# S-ONDAS-ESPIN.net
KiCad netlist of a schematic drawn in Altium Designer
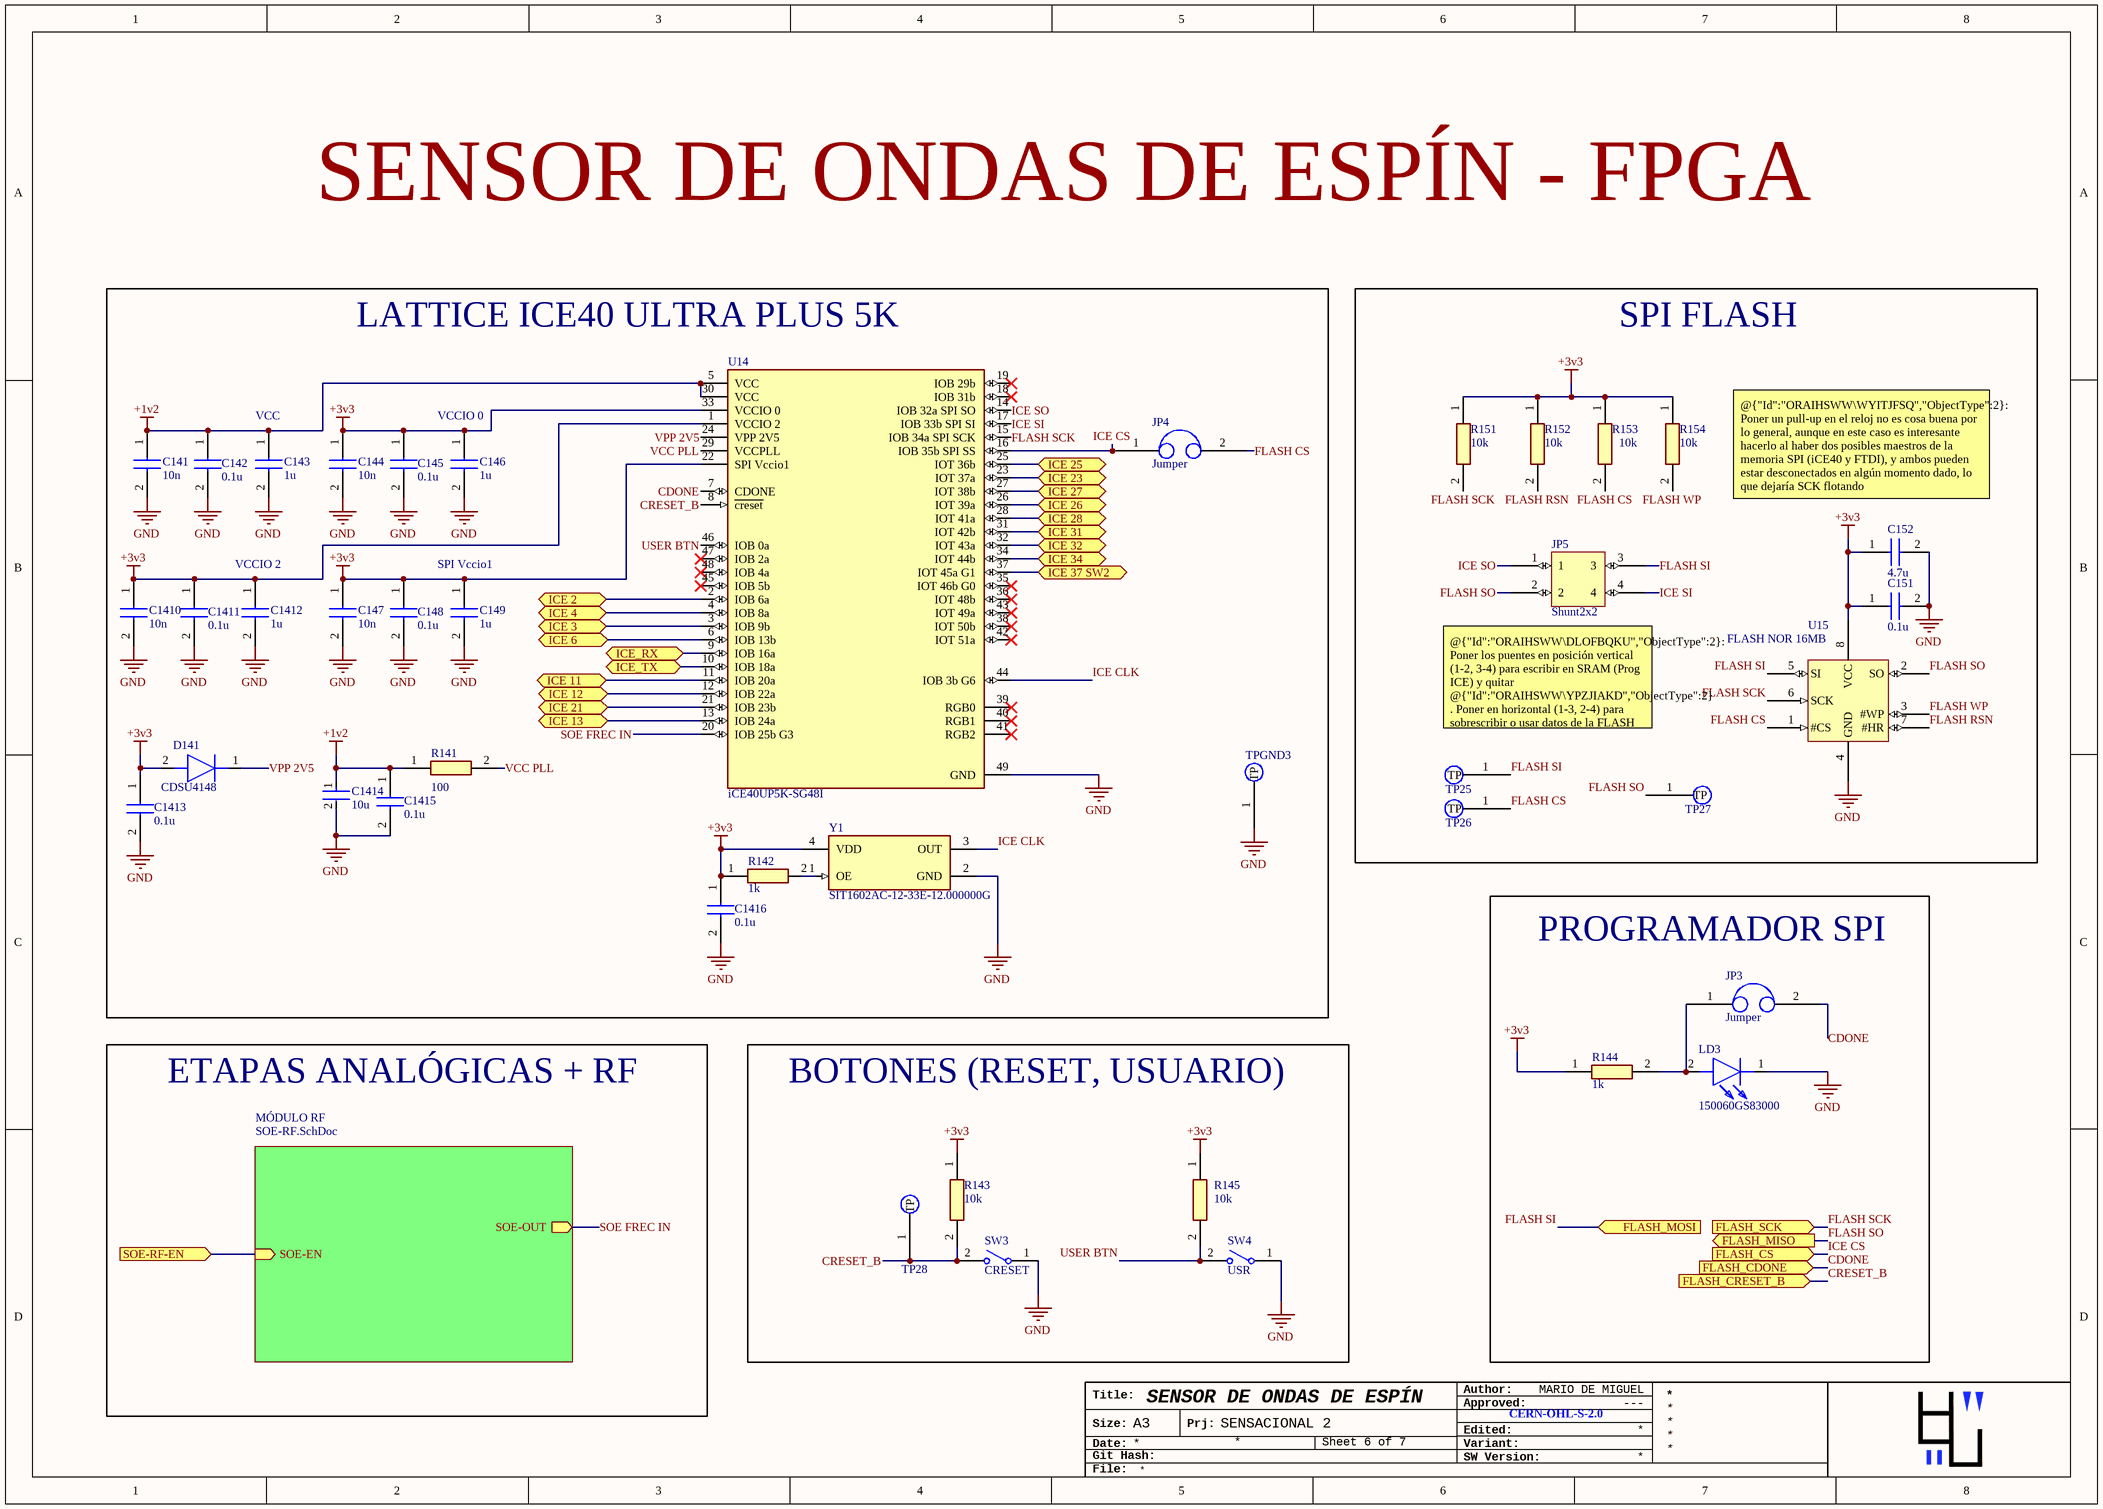
[diagram p0: S-ONDAS-ESPIN.SchDoc]

(export (version "E")
  (design (tool "Eeschema 10.0.6"))
  (components
    (comp (ref "C141")
      (value "10n")
      (footprint "SamacSys:CAPC1005X55N")
      (description "Capacitor")
      (fields (field (name "MANUFACTURER_PART_NUMBER") "GXT155R71E103KE01D"))
      (libsource (lib "*") (part "GXT155R71E103KE01D"))
    )
    (comp (ref "C142")
      (value "0.1u")
      (footprint "SamacSys:CAPC1005X22N")
      (description "Capacitor")
      (fields
        (field (name "MANUFACTURER_PART_NUMBER") "GRM152R61A104KE19D")
        (field (name "MOUSER PART NUMBER") "81-GRM152R61A104KE9D")
      )
      (libsource (lib "*") (part "GRM152R61A104KE19D"))
    )
    (comp (ref "C143")
      (value "1u")
      (footprint "SamacSys:GRM15x")
      (description "Capacitor")
      (fields (field (name "MANUFACTURER_PART_NUMBER") "GRM155C71C105ME11J"))
      (libsource (lib "*") (part "GRM155C71C105ME11J"))
    )
    (comp (ref "C144")
      (value "10n")
      (footprint "SamacSys:CAPC1005X55N")
      (description "Capacitor")
      (fields (field (name "MANUFACTURER_PART_NUMBER") "GXT155R71E103KE01D"))
      (libsource (lib "*") (part "GXT155R71E103KE01D"))
    )
    (comp (ref "C145")
      (value "0.1u")
      (footprint "SamacSys:CAPC1005X22N")
      (description "Capacitor")
      (fields
        (field (name "MANUFACTURER_PART_NUMBER") "GRM152R61A104KE19D")
        (field (name "MOUSER PART NUMBER") "81-GRM152R61A104KE9D")
      )
      (libsource (lib "*") (part "GRM152R61A104KE19D"))
    )
    (comp (ref "C146")
      (value "1u")
      (footprint "SamacSys:GRM15x")
      (description "Capacitor")
      (fields (field (name "MANUFACTURER_PART_NUMBER") "GRM155C71C105ME11J"))
      (libsource (lib "*") (part "GRM155C71C105ME11J"))
    )
    (comp (ref "C147")
      (value "10n")
      (footprint "SamacSys:CAPC1005X55N")
      (description "Capacitor")
      (fields (field (name "MANUFACTURER_PART_NUMBER") "GXT155R71E103KE01D"))
      (libsource (lib "*") (part "GXT155R71E103KE01D"))
    )
    (comp (ref "C148")
      (value "0.1u")
      (footprint "SamacSys:CAPC1005X22N")
      (description "Capacitor")
      (fields
        (field (name "MANUFACTURER_PART_NUMBER") "GRM152R61A104KE19D")
        (field (name "MOUSER PART NUMBER") "81-GRM152R61A104KE9D")
      )
      (libsource (lib "*") (part "GRM152R61A104KE19D"))
    )
    (comp (ref "C149")
      (value "1u")
      (footprint "SamacSys:GRM15x")
      (description "Capacitor")
      (fields (field (name "MANUFACTURER_PART_NUMBER") "GRM155C71C105ME11J"))
      (libsource (lib "*") (part "GRM155C71C105ME11J"))
    )
    (comp (ref "C151")
      (value "0.1u")
      (footprint "SamacSys:CAPC1005X22N")
      (description "Capacitor")
      (fields
        (field (name "MANUFACTURER_PART_NUMBER") "GRM152R61A104KE19D")
        (field (name "MOUSER PART NUMBER") "81-GRM152R61A104KE9D")
      )
      (libsource (lib "*") (part "GRM152R61A104KE19D"))
    )
    (comp (ref "C152")
      (value "4.7u")
      (footprint "SamacSys:C0805")
      (description "Capacitor")
      (fields
        (field (name "MANUFACTURER_PART_NUMBER") "C0805X475J8RACAUTO")
        (field (name "MOUSER PART NUMBER") "80-C0805X475J8RAUTO")
      )
      (libsource (lib "*") (part "C0805X475J8RACAUTO"))
    )
    (comp (ref "C1410")
      (value "10n")
      (footprint "SamacSys:CAPC1005X55N")
      (description "Capacitor")
      (fields (field (name "MANUFACTURER_PART_NUMBER") "GXT155R71E103KE01D"))
      (libsource (lib "*") (part "GXT155R71E103KE01D"))
    )
    (comp (ref "C1411")
      (value "0.1u")
      (footprint "SamacSys:CAPC1005X22N")
      (description "Capacitor")
      (fields
        (field (name "MANUFACTURER_PART_NUMBER") "GRM152R61A104KE19D")
        (field (name "MOUSER PART NUMBER") "81-GRM152R61A104KE9D")
      )
      (libsource (lib "*") (part "GRM152R61A104KE19D"))
    )
    (comp (ref "C1412")
      (value "1u")
      (footprint "SamacSys:GRM15x")
      (description "Capacitor")
      (fields (field (name "MANUFACTURER_PART_NUMBER") "GRM155C71C105ME11J"))
      (libsource (lib "*") (part "GRM155C71C105ME11J"))
    )
    (comp (ref "C1413")
      (value "0.1u")
      (footprint "SamacSys:CAPC1005X22N")
      (description "Capacitor")
      (fields
        (field (name "MANUFACTURER_PART_NUMBER") "GRM152R61A104KE19D")
        (field (name "MOUSER PART NUMBER") "81-GRM152R61A104KE9D")
      )
      (libsource (lib "*") (part "GRM152R61A104KE19D"))
    )
    (comp (ref "C1414")
      (value "10u")
      (footprint "FP-C2012-125-0_2-MFG")
      (description "Multilayer Ceramic Capacitors 10μF ±10% 10V X7R SMD 0805")
      (fields (field (name "TOLERANCE") "10%") (field (name "VOLTAGE") "10V"))
      (libsource (lib "Altium Content Vault") (part "b4654b650e69147ec39a6b967a45e02"))
    )
    (comp (ref "C1415")
      (value "0.1u")
      (footprint "SamacSys:CAPC1005X22N")
      (description "Capacitor")
      (fields
        (field (name "MANUFACTURER_PART_NUMBER") "GRM152R61A104KE19D")
        (field (name "MOUSER PART NUMBER") "81-GRM152R61A104KE9D")
      )
      (libsource (lib "*") (part "GRM152R61A104KE19D"))
    )
    (comp (ref "C1416")
      (value "0.1u")
      (footprint "SamacSys:CAPC1005X22N")
      (description "Capacitor")
      (fields
        (field (name "MANUFACTURER_PART_NUMBER") "GRM152R61A104KE19D")
        (field (name "MOUSER PART NUMBER") "81-GRM152R61A104KE9D")
      )
      (libsource (lib "*") (part "GRM152R61A104KE19D"))
    )
    (comp (ref "D141")
      (value "CDSU4148")
      (footprint "SamacSys:DIOM179X85N")
      (description "Diode")
      (fields (field (name "MOUSER PART NUMBER") "750-CDSU4148"))
      (libsource (lib "*") (part "CDSU4148"))
    )
    (comp (ref "JP3") (value "Jumper") (footprint "JUMPER_SHUNT") (libsource (lib "headers") (part "Shunt")))
    (comp (ref "JP4") (value "Jumper") (footprint "JUMPER_SHUNT") (libsource (lib "headers") (part "Shunt")))
    (comp (ref "JP5")
      (value "Shunt2x2")
      (footprint "JUMPER_SHUNT2X2")
      (libsource (lib "headers") (part "Shunt2x2"))
    )
    (comp (ref "LD3")
      (value "150060GS83000")
      (footprint "SamacSys:LEDC1608X95N")
      (description "LED")
      (libsource (lib "*") (part "150060GS83000"))
    )
    (comp (ref "R141")
      (value "100")
      (footprint "SamacSys:RESC1608X50N")
      (description "Resistor")
      (fields
        (field (name "MANUFACTURER_PART_NUMBER") "RCG0603100RJNEA")
        (field (name "MOUSER PART NUMBER") "71-RCG0603100RJNEA")
      )
      (libsource (lib "*") (part "RCG0603100RJNEA"))
    )
    (comp (ref "R142")
      (value "1k")
      (footprint "SamacSys:ERA6AEB101V")
      (description "Resistor")
      (fields
        (field (name "MANUFACTURER_PART_NUMBER") "ERA-6ARW102V")
        (field (name "MOUSER PART NUMBER") "667-ERA-6ARW102V")
      )
      (libsource (lib "*") (part "ERA-6ARW102V"))
    )
    (comp (ref "R143")
      (value "10k")
      (footprint "SamacSys:RESC1005X40N")
      (description "Resistor")
      (fields
        (field (name "MANUFACTURER_PART_NUMBER") "RCA040210K0JNED")
        (field (name "MOUSER PART NUMBER") "71-RCA040210K0JNED")
      )
      (libsource (lib "*") (part "RCA040210K0JNED"))
    )
    (comp (ref "R144")
      (value "1k")
      (footprint "SamacSys:ERA6AEB101V")
      (description "Resistor")
      (fields
        (field (name "MANUFACTURER_PART_NUMBER") "ERA-6ARW102V")
        (field (name "MOUSER PART NUMBER") "667-ERA-6ARW102V")
      )
      (libsource (lib "*") (part "ERA-6ARW102V"))
    )
    (comp (ref "R145")
      (value "10k")
      (footprint "SamacSys:RESC1005X40N")
      (description "Resistor")
      (fields
        (field (name "MANUFACTURER_PART_NUMBER") "RCA040210K0JNED")
        (field (name "MOUSER PART NUMBER") "71-RCA040210K0JNED")
      )
      (libsource (lib "*") (part "RCA040210K0JNED"))
    )
    (comp (ref "R151")
      (value "10k")
      (footprint "SamacSys:RESC1005X40N")
      (description "Resistor")
      (fields
        (field (name "MANUFACTURER_PART_NUMBER") "RCA040210K0JNED")
        (field (name "MOUSER PART NUMBER") "71-RCA040210K0JNED")
      )
      (libsource (lib "*") (part "RCA040210K0JNED"))
    )
    (comp (ref "R152")
      (value "10k")
      (footprint "SamacSys:RESC1005X40N")
      (description "Resistor")
      (fields
        (field (name "MANUFACTURER_PART_NUMBER") "RCA040210K0JNED")
        (field (name "MOUSER PART NUMBER") "71-RCA040210K0JNED")
      )
      (libsource (lib "*") (part "RCA040210K0JNED"))
    )
    (comp (ref "R153")
      (value "10k")
      (footprint "SamacSys:RESC1005X40N")
      (description "Resistor")
      (fields
        (field (name "MANUFACTURER_PART_NUMBER") "RCA040210K0JNED")
        (field (name "MOUSER PART NUMBER") "71-RCA040210K0JNED")
      )
      (libsource (lib "*") (part "RCA040210K0JNED"))
    )
    (comp (ref "R154")
      (value "10k")
      (footprint "SamacSys:RESC1005X40N")
      (description "Resistor")
      (fields
        (field (name "MANUFACTURER_PART_NUMBER") "RCA040210K0JNED")
        (field (name "MOUSER PART NUMBER") "71-RCA040210K0JNED")
      )
      (libsource (lib "*") (part "RCA040210K0JNED"))
    )
    (comp (ref "SW3")
      (value "CRESET")
      (footprint "434121025816")
      (description "Switch Tactile Spst-no 0.05A 12V")
      (libsource (lib "Altium Content Vault") (part "SPST-NO_2P"))
    )
    (comp (ref "SW4")
      (value "USR")
      (footprint "434121025816")
      (description "Switch Tactile Spst-no 0.05A 12V")
      (libsource (lib "Altium Content Vault") (part "SPST-NO_2P"))
    )
    (comp (ref "TP25")
      (value "Testpoint")
      (footprint "TESTPOINT_SMD")
      (libsource (lib "headers") (part "Testpoint"))
    )
    (comp (ref "TP26")
      (value "Testpoint")
      (footprint "TESTPOINT_SMD")
      (libsource (lib "headers") (part "Testpoint"))
    )
    (comp (ref "TP27")
      (value "Testpoint")
      (footprint "TESTPOINT_SMD")
      (libsource (lib "headers") (part "Testpoint"))
    )
    (comp (ref "TP28")
      (value "Testpoint")
      (footprint "Testpoint_TH")
      (libsource (lib "headers") (part "Testpoint"))
    )
    (comp (ref "TPGND3")
      (value "Testpoint")
      (footprint "Testpoint_TH")
      (libsource (lib "headers") (part "Testpoint"))
    )
    (comp (ref "U14")
      (value "iCE40UP5K-SG48I")
      (footprint "FP-QFN-48-IPC_C")
      (description "ICE40-ULTRAPLUS, 5280 LUTS, 1.2V")
      (fields
        (field (name "MANUFACTURER") "Lattice")
        (field (name "OCTOPART") "https://octopart.com/ice40up5k-sg48i-lattice+semiconductor-87369311")
      )
      (libsource (lib "Altium Content Vault") (part "90c839ece6b9b86f6dd6a74a4566a88"))
    )
    (comp (ref "U15")
      (value "FLASH NOR 16MB")
      (footprint "SOIC127P790X216-8N:SOIC127P790X216-8N")
      (libsource (lib "IS25LP016D-JBLE") (part "IS25LP016D-JBLE"))
    )
    (comp (ref "Y1")
      (value "SIT1602AC-12-33E-12.000000G")
      (footprint "FP-SiT1602-1-MFG")
      (description "MEMS OSC XO 12.0000MHZ LVCMOS")
      (libsource (lib "Altium Content Vault") (part "ab5556b3551095060e619687c253883"))
    )
  )
  (nets
    (net (code "1") (name "+1v2") (class "Default")
      (node (ref "C141") (pin "1") (pinfunction "1_1") (pintype "passive"))
      (node (ref "C1414") (pin "1") (pinfunction "1_1") (pintype "passive"))
      (node (ref "C1415") (pin "1") (pinfunction "1_1") (pintype "passive"))
      (node (ref "C142") (pin "1") (pinfunction "1_1") (pintype "passive"))
      (node (ref "C143") (pin "1") (pinfunction "1_1") (pintype "passive"))
      (node (ref "R141") (pin "1") (pinfunction "1_1") (pintype "passive"))
      (node (ref "U14") (pin "30") (pinfunction "VCC_30") (pintype "power_in"))
      (node (ref "U14") (pin "5") (pinfunction "VCC_5") (pintype "power_in"))
    )
    (net (code "2") (name "+3v3") (class "Default")
      (node (ref "C1410") (pin "1") (pinfunction "1_1") (pintype "passive"))
      (node (ref "C1411") (pin "1") (pinfunction "1_1") (pintype "passive"))
      (node (ref "C1412") (pin "1") (pinfunction "1_1") (pintype "passive"))
      (node (ref "C1413") (pin "1") (pinfunction "1_1") (pintype "passive"))
      (node (ref "C1416") (pin "1") (pinfunction "1_1") (pintype "passive"))
      (node (ref "C144") (pin "1") (pinfunction "1_1") (pintype "passive"))
      (node (ref "C145") (pin "1") (pinfunction "1_1") (pintype "passive"))
      (node (ref "C146") (pin "1") (pinfunction "1_1") (pintype "passive"))
      (node (ref "C147") (pin "1") (pinfunction "1_1") (pintype "passive"))
      (node (ref "C148") (pin "1") (pinfunction "1_1") (pintype "passive"))
      (node (ref "C149") (pin "1") (pinfunction "1_1") (pintype "passive"))
      (node (ref "C151") (pin "1") (pinfunction "1_1") (pintype "passive"))
      (node (ref "C152") (pin "1") (pinfunction "1_1") (pintype "passive"))
      (node (ref "D141") (pin "2") (pinfunction "A_2") (pintype "passive"))
      (node (ref "R142") (pin "1") (pinfunction "1_1") (pintype "passive"))
      (node (ref "R143") (pin "1") (pinfunction "1_1") (pintype "passive"))
      (node (ref "R144") (pin "1") (pinfunction "1_1") (pintype "passive"))
      (node (ref "R145") (pin "1") (pinfunction "1_1") (pintype "passive"))
      (node (ref "R151") (pin "1") (pinfunction "1_1") (pintype "passive"))
      (node (ref "R152") (pin "1") (pinfunction "1_1") (pintype "passive"))
      (node (ref "R153") (pin "1") (pinfunction "1_1") (pintype "passive"))
      (node (ref "R154") (pin "1") (pinfunction "1_1") (pintype "passive"))
      (node (ref "U14") (pin "1") (pinfunction "VCCIO_2_1") (pintype "power_in"))
      (node (ref "U14") (pin "22") (pinfunction "SPI_Vccio1_22") (pintype "power_in"))
      (node (ref "U14") (pin "33") (pinfunction "VCCIO_0_33") (pintype "power_in"))
      (node (ref "U15") (pin "8") (pinfunction "VCC_8") (pintype "power_in"))
      (node (ref "Y1") (pin "4") (pinfunction "VDD_4") (pintype "power_in"))
    )
    (net (code "3") (name "/CDONE") (class "Default")
      (node (ref "JP3") (pin "2") (pintype "passive"))
      (node (ref "U14") (pin "7") (pinfunction "CDONE_7") (pintype "bidirectional"))
    )
    (net (code "4") (name "/CRESET_B") (class "Default")
      (node (ref "R143") (pin "2") (pinfunction "2_2") (pintype "passive"))
      (node (ref "SW3") (pin "2") (pinfunction "2_2") (pintype "passive"))
      (node (ref "TP28") (pin "1") (pinfunction "TP_1") (pintype "passive"))
      (node (ref "U14") (pin "8") (pinfunction "~{creset}_8") (pintype "input"))
    )
    (net (code "5") (name "/FLASH CS") (class "Default")
      (node (ref "JP4") (pin "2") (pintype "passive"))
      (node (ref "R153") (pin "2") (pinfunction "2_2") (pintype "passive"))
      (node (ref "TP26") (pin "1") (pinfunction "TP_1") (pintype "passive"))
      (node (ref "U15") (pin "1") (pinfunction "#CS_1") (pintype "input"))
    )
    (net (code "6") (name "/FLASH RSN") (class "Default")
      (node (ref "R152") (pin "2") (pinfunction "2_2") (pintype "passive"))
      (node (ref "U15") (pin "7") (pinfunction "#HR_7") (pintype "bidirectional"))
    )
    (net (code "7") (name "/FLASH SCK") (class "Default")
      (node (ref "R151") (pin "2") (pinfunction "2_2") (pintype "passive"))
      (node (ref "U14") (pin "15") (pinfunction "IOB_34a_SPI_SCK_15") (pintype "bidirectional"))
      (node (ref "U15") (pin "6") (pinfunction "SCK_6") (pintype "input"))
    )
    (net (code "8") (name "/FLASH SI") (class "Default")
      (node (ref "JP5") (pin "3") (pinfunction "3_3") (pintype "bidirectional"))
      (node (ref "TP25") (pin "1") (pinfunction "TP_1") (pintype "passive"))
      (node (ref "U15") (pin "5") (pinfunction "SI_5") (pintype "bidirectional"))
    )
    (net (code "9") (name "/FLASH SO") (class "Default")
      (node (ref "JP5") (pin "2") (pinfunction "2_2") (pintype "bidirectional"))
      (node (ref "TP27") (pin "1") (pinfunction "TP_1") (pintype "passive"))
      (node (ref "U15") (pin "2") (pinfunction "SO_2") (pintype "bidirectional"))
    )
    (net (code "10") (name "/FLASH WP") (class "Default")
      (node (ref "R154") (pin "2") (pinfunction "2_2") (pintype "passive"))
      (node (ref "U15") (pin "3") (pinfunction "#WP_3") (pintype "bidirectional"))
    )
    (net (code "11") (name "/ICE 2") (class "Default")
      (node (ref "U14") (pin "2") (pinfunction "IOB_6a_2") (pintype "bidirectional"))
    )
    (net (code "12") (name "/ICE 3") (class "Default")
      (node (ref "U14") (pin "3") (pinfunction "IOB_9b_3") (pintype "bidirectional"))
    )
    (net (code "13") (name "/ICE 4") (class "Default")
      (node (ref "U14") (pin "4") (pinfunction "IOB_8a_4") (pintype "bidirectional"))
    )
    (net (code "14") (name "/ICE 6") (class "Default")
      (node (ref "U14") (pin "6") (pinfunction "IOB_13b_6") (pintype "bidirectional"))
    )
    (net (code "15") (name "/ICE 11") (class "Default")
      (node (ref "U14") (pin "11") (pinfunction "IOB_20a_11") (pintype "bidirectional"))
    )
    (net (code "16") (name "/ICE 12") (class "Default")
      (node (ref "U14") (pin "12") (pinfunction "IOB_22a_12") (pintype "bidirectional"))
    )
    (net (code "17") (name "/ICE 13") (class "Default")
      (node (ref "U14") (pin "13") (pinfunction "IOB_24a_13") (pintype "bidirectional"))
    )
    (net (code "18") (name "/ICE 21") (class "Default")
      (node (ref "U14") (pin "21") (pinfunction "IOB_23b_21") (pintype "bidirectional"))
    )
    (net (code "19") (name "/ICE 23") (class "Default")
      (node (ref "U14") (pin "23") (pinfunction "IOT_37a_23") (pintype "bidirectional"))
    )
    (net (code "20") (name "/ICE 25") (class "Default")
      (node (ref "U14") (pin "25") (pinfunction "IOT_36b_25") (pintype "bidirectional"))
    )
    (net (code "21") (name "/ICE 26") (class "Default")
      (node (ref "U14") (pin "26") (pinfunction "IOT_39a_26") (pintype "bidirectional"))
    )
    (net (code "22") (name "/ICE 27") (class "Default")
      (node (ref "U14") (pin "27") (pinfunction "IOT_38b_27") (pintype "bidirectional"))
    )
    (net (code "23") (name "/ICE 28") (class "Default")
      (node (ref "U14") (pin "28") (pinfunction "IOT_41a_28") (pintype "bidirectional"))
    )
    (net (code "24") (name "/ICE 31") (class "Default")
      (node (ref "U14") (pin "31") (pinfunction "IOT_42b_31") (pintype "bidirectional"))
    )
    (net (code "25") (name "/ICE 32") (class "Default")
      (node (ref "U14") (pin "32") (pinfunction "IOT_43a_32") (pintype "bidirectional"))
    )
    (net (code "26") (name "/ICE 34") (class "Default")
      (node (ref "U14") (pin "34") (pinfunction "IOT_44b_34") (pintype "bidirectional"))
    )
    (net (code "27") (name "/ICE 37 SW2") (class "Default")
      (node (ref "U14") (pin "37") (pinfunction "IOT_45a_G1_37") (pintype "bidirectional"))
    )
    (net (code "28") (name "/ICE CLK") (class "Default")
      (node (ref "U14") (pin "44") (pinfunction "IOB_3b_G6_44") (pintype "bidirectional"))
      (node (ref "Y1") (pin "3") (pinfunction "OUT_3") (pintype "passive"))
    )
    (net (code "29") (name "/ICE CS") (class "Default")
      (node (ref "JP4") (pin "1") (pinfunction "16_1") (pintype "passive"))
      (node (ref "U14") (pin "16") (pinfunction "IOB_35b_SPI_SS_16") (pintype "bidirectional"))
    )
    (net (code "30") (name "/ICE SI") (class "Default")
      (node (ref "JP5") (pin "4") (pinfunction "4_4") (pintype "bidirectional"))
      (node (ref "U14") (pin "17") (pinfunction "IOB_33b_SPI_SI_17") (pintype "bidirectional"))
    )
    (net (code "31") (name "/ICE SO") (class "Default")
      (node (ref "JP5") (pin "1") (pinfunction "1_1") (pintype "bidirectional"))
      (node (ref "U14") (pin "14") (pinfunction "IOB_32a_SPI_SO_14") (pintype "bidirectional"))
    )
    (net (code "32") (name "/ICE_RX") (class "Default")
      (node (ref "U14") (pin "9") (pinfunction "IOB_16a_9") (pintype "bidirectional"))
    )
    (net (code "33") (name "/ICE_TX") (class "Default")
      (node (ref "U14") (pin "10") (pinfunction "IOB_18a_10") (pintype "bidirectional"))
    )
    (net (code "34") (name "/SOE FREC IN") (class "Default")
      (node (ref "U14") (pin "20") (pinfunction "IOB_25b_G3_20") (pintype "bidirectional"))
    )
    (net (code "36") (name "/USER BTN") (class "Default")
      (node (ref "R145") (pin "2") (pinfunction "2_2") (pintype "passive"))
      (node (ref "SW4") (pin "2") (pinfunction "2_2") (pintype "passive"))
      (node (ref "U14") (pin "46") (pinfunction "IOB_0a_46") (pintype "bidirectional"))
    )
    (net (code "37") (name "/VCC PLL") (class "Default")
      (node (ref "R141") (pin "2") (pinfunction "2_2") (pintype "passive"))
      (node (ref "U14") (pin "29") (pinfunction "VCCPLL_29") (pintype "power_in"))
    )
    (net (code "38") (name "/VPP 2V5") (class "Default")
      (node (ref "D141") (pin "1") (pinfunction "K_1") (pintype "passive"))
      (node (ref "U14") (pin "24") (pinfunction "VPP_2V5_24") (pintype "power_in"))
    )
    (net (code "39") (name "GND") (class "Default")
      (node (ref "C141") (pin "2") (pinfunction "2_2") (pintype "passive"))
      (node (ref "C1410") (pin "2") (pinfunction "2_2") (pintype "passive"))
      (node (ref "C1411") (pin "2") (pinfunction "2_2") (pintype "passive"))
      (node (ref "C1412") (pin "2") (pinfunction "2_2") (pintype "passive"))
      (node (ref "C1413") (pin "2") (pinfunction "2_2") (pintype "passive"))
      (node (ref "C1414") (pin "2") (pinfunction "2_2") (pintype "passive"))
      (node (ref "C1415") (pin "2") (pinfunction "2_2") (pintype "passive"))
      (node (ref "C1416") (pin "2") (pinfunction "2_2") (pintype "passive"))
      (node (ref "C142") (pin "2") (pinfunction "2_2") (pintype "passive"))
      (node (ref "C143") (pin "2") (pinfunction "2_2") (pintype "passive"))
      (node (ref "C144") (pin "2") (pinfunction "2_2") (pintype "passive"))
      (node (ref "C145") (pin "2") (pinfunction "2_2") (pintype "passive"))
      (node (ref "C146") (pin "2") (pinfunction "2_2") (pintype "passive"))
      (node (ref "C147") (pin "2") (pinfunction "2_2") (pintype "passive"))
      (node (ref "C148") (pin "2") (pinfunction "2_2") (pintype "passive"))
      (node (ref "C149") (pin "2") (pinfunction "2_2") (pintype "passive"))
      (node (ref "C151") (pin "2") (pinfunction "2_2") (pintype "passive"))
      (node (ref "C152") (pin "2") (pinfunction "2_2") (pintype "passive"))
      (node (ref "LD3") (pin "1") (pinfunction "K_1") (pintype "passive"))
      (node (ref "SW3") (pin "1") (pinfunction "1_1") (pintype "passive"))
      (node (ref "SW4") (pin "1") (pinfunction "1_1") (pintype "passive"))
      (node (ref "TPGND3") (pin "1") (pinfunction "TP_1") (pintype "passive"))
      (node (ref "U14") (pin "49") (pinfunction "GND_49") (pintype "power_in"))
      (node (ref "U15") (pin "4") (pinfunction "GND_4") (pintype "power_in"))
      (node (ref "Y1") (pin "2") (pinfunction "GND_2") (pintype "power_in"))
    )
    (net (code "40") (name "Net-(JP3-16)") (class "Default")
      (node (ref "JP3") (pin "1") (pinfunction "16_1") (pintype "passive"))
      (node (ref "LD3") (pin "2") (pinfunction "A_2") (pintype "passive"))
      (node (ref "R144") (pin "2") (pinfunction "2_2") (pintype "passive"))
    )
    (net (code "41") (name "Net-(Y1-OE)") (class "Default")
      (node (ref "R142") (pin "2") (pinfunction "2_2") (pintype "passive"))
      (node (ref "Y1") (pin "1") (pinfunction "OE_1") (pintype "input"))
    )
    (net (code "42") (name "unconnected-(U14-IOB_2a-Pad47)") (class "Default")
      (node (ref "U14") (pin "47") (pinfunction "IOB_2a_47") (pintype "bidirectional+no_connect"))
    )
    (net (code "43") (name "unconnected-(U14-IOB_4a-Pad48)") (class "Default")
      (node (ref "U14") (pin "48") (pinfunction "IOB_4a_48") (pintype "bidirectional+no_connect"))
    )
    (net (code "44") (name "unconnected-(U14-IOB_5b-Pad45)") (class "Default")
      (node (ref "U14") (pin "45") (pinfunction "IOB_5b_45") (pintype "bidirectional+no_connect"))
    )
    (net (code "45") (name "unconnected-(U14-IOB_29b-Pad19)") (class "Default")
      (node (ref "U14") (pin "19") (pinfunction "IOB_29b_19") (pintype "bidirectional+no_connect"))
    )
    (net (code "46") (name "unconnected-(U14-IOB_31b-Pad18)") (class "Default")
      (node (ref "U14") (pin "18") (pinfunction "IOB_31b_18") (pintype "bidirectional+no_connect"))
    )
    (net (code "47") (name "unconnected-(U14-IOT_46b_G0-Pad35)") (class "Default")
      (node (ref "U14") (pin "35") (pinfunction "IOT_46b_G0_35") (pintype "bidirectional+no_connect"))
    )
    (net (code "48") (name "unconnected-(U14-IOT_48b-Pad36)") (class "Default")
      (node (ref "U14") (pin "36") (pinfunction "IOT_48b_36") (pintype "bidirectional+no_connect"))
    )
    (net (code "49") (name "unconnected-(U14-IOT_49a-Pad43)") (class "Default")
      (node (ref "U14") (pin "43") (pinfunction "IOT_49a_43") (pintype "bidirectional+no_connect"))
    )
    (net (code "50") (name "unconnected-(U14-IOT_50b-Pad38)") (class "Default")
      (node (ref "U14") (pin "38") (pinfunction "IOT_50b_38") (pintype "bidirectional+no_connect"))
    )
    (net (code "51") (name "unconnected-(U14-IOT_51a-Pad42)") (class "Default")
      (node (ref "U14") (pin "42") (pinfunction "IOT_51a_42") (pintype "bidirectional+no_connect"))
    )
    (net (code "52") (name "unconnected-(U14-RGB0-Pad39)") (class "Default")
      (node (ref "U14") (pin "39") (pinfunction "RGB0_39") (pintype "open_collector+no_connect"))
    )
    (net (code "53") (name "unconnected-(U14-RGB1-Pad40)") (class "Default")
      (node (ref "U14") (pin "40") (pinfunction "RGB1_40") (pintype "open_collector+no_connect"))
    )
    (net (code "54") (name "unconnected-(U14-RGB2-Pad41)") (class "Default")
      (node (ref "U14") (pin "41") (pinfunction "RGB2_41") (pintype "open_collector+no_connect"))
    )
  )
)
